# schematic.net
KiCad netlist of a schematic drawn in Altium Designer
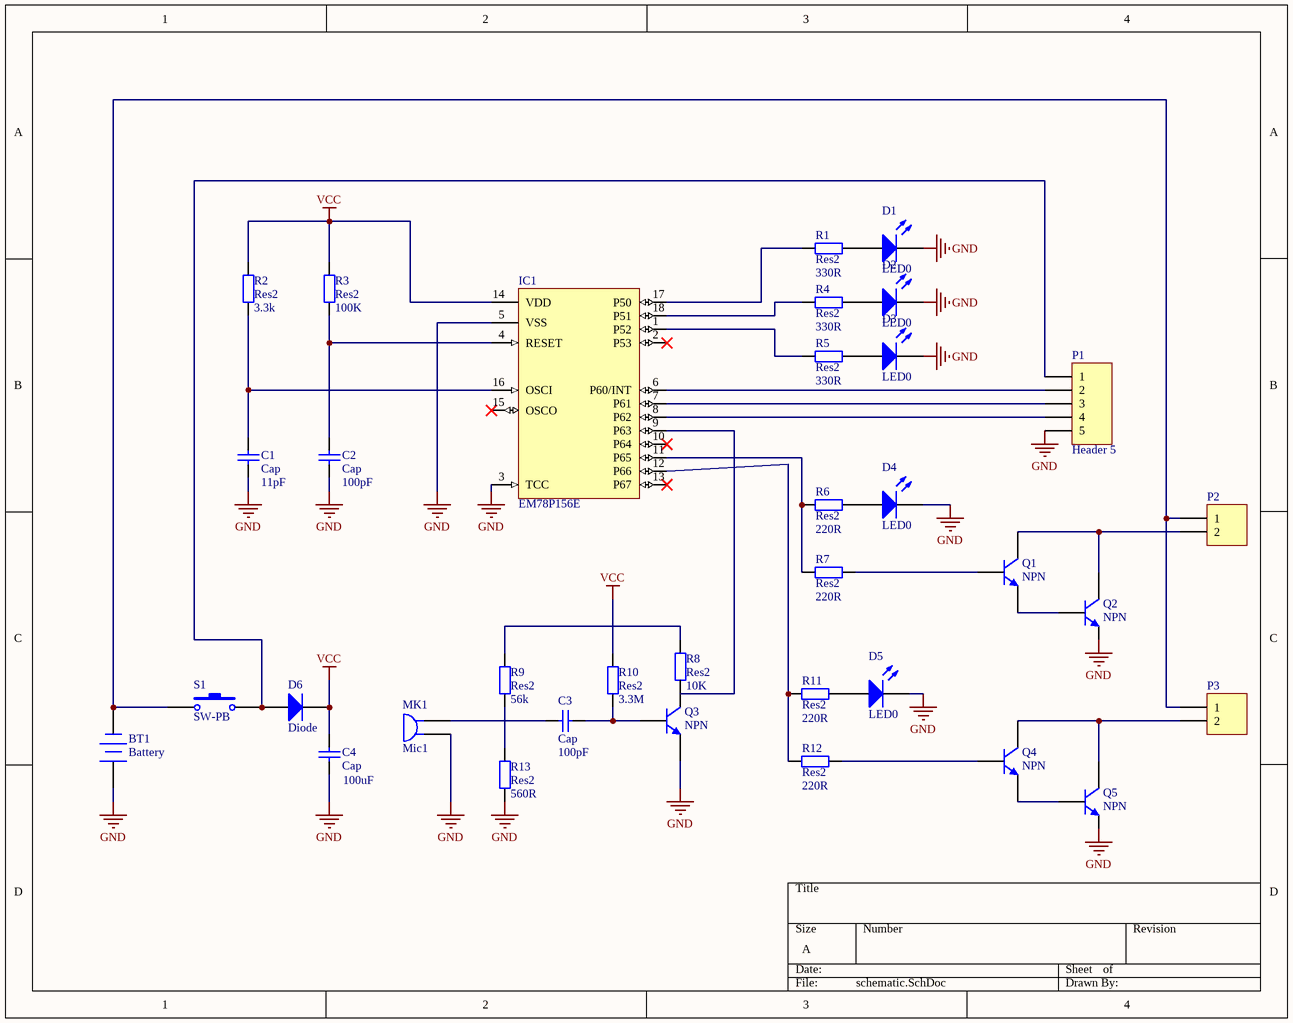
[diagram p0: schematic.SchDoc]

(export (version "E")
  (design (tool "Eeschema 10.0.6"))
  (components
    (comp (ref "BT1")
      (value "Battery")
      (footprint "BAT-2")
      (description "Multicell Battery")
      (fields (field (name "PUBLISHER") "Altium Limited"))
      (libsource (lib "Miscellaneous Devices") (part "Battery"))
    )
    (comp (ref "C1")
      (value "Cap")
      (footprint "RAD-0.3")
      (description "Capacitor")
      (fields (field (name "ALTIUM_VALUE") "11pF") (field (name "PUBLISHER") "Altium Limited"))
      (libsource (lib "Miscellaneous Devices") (part "Cap"))
    )
    (comp (ref "C2")
      (value "Cap")
      (footprint "RAD-0.3")
      (description "Capacitor")
      (fields (field (name "ALTIUM_VALUE") "100pF") (field (name "PUBLISHER") "Altium Limited"))
      (libsource (lib "Miscellaneous Devices") (part "Cap"))
    )
    (comp (ref "C3")
      (value "Cap")
      (footprint "RAD-0.3")
      (description "Capacitor")
      (fields (field (name "ALTIUM_VALUE") "100pF") (field (name "PUBLISHER") "Altium Limited"))
      (libsource (lib "Miscellaneous Devices") (part "Cap"))
    )
    (comp (ref "C4")
      (value "Cap")
      (footprint "RAD-0.3")
      (description "Capacitor")
      (fields (field (name "ALTIUM_VALUE") "100uF") (field (name "PUBLISHER") "Altium Limited"))
      (libsource (lib "Miscellaneous Devices") (part "Cap"))
    )
    (comp (ref "D1")
      (value "LED0")
      (footprint "LED-0")
      (description "Typical INFRARED GaAs LED")
      (fields (field (name "PUBLISHER") "Altium Limited"))
      (libsource (lib "Miscellaneous Devices") (part "LED0"))
    )
    (comp (ref "D2")
      (value "LED0")
      (footprint "LED-0")
      (description "Typical INFRARED GaAs LED")
      (fields (field (name "PUBLISHER") "Altium Limited"))
      (libsource (lib "Miscellaneous Devices") (part "LED0"))
    )
    (comp (ref "D3")
      (value "LED0")
      (footprint "LED-0")
      (description "Typical INFRARED GaAs LED")
      (fields (field (name "PUBLISHER") "Altium Limited"))
      (libsource (lib "Miscellaneous Devices") (part "LED0"))
    )
    (comp (ref "D4")
      (value "LED0")
      (footprint "LED-0")
      (description "Typical INFRARED GaAs LED")
      (fields (field (name "PUBLISHER") "Altium Limited"))
      (libsource (lib "Miscellaneous Devices") (part "LED0"))
    )
    (comp (ref "D5")
      (value "LED0")
      (footprint "LED-0")
      (description "Typical INFRARED GaAs LED")
      (fields (field (name "PUBLISHER") "Altium Limited"))
      (libsource (lib "Miscellaneous Devices") (part "LED0"))
    )
    (comp (ref "D6")
      (value "Diode")
      (footprint "SMC")
      (description "Default Diode")
      (fields (field (name "PUBLISHER") "Altium Limited"))
      (libsource (lib "Miscellaneous Devices") (part "Diode"))
    )
    (comp (ref "IC1")
      (value "EM78P156E")
      (footprint "DIP18")
      (libsource (lib "MC_personal") (part "EM78P156E"))
    )
    (comp (ref "MK1")
      (value "Mic1")
      (footprint "PIN2")
      (description "Microphone")
      (fields (field (name "PUBLISHER") "Altium Limited"))
      (libsource (lib "Miscellaneous Devices") (part "Mic1"))
    )
    (comp (ref "P1")
      (value "Header 5")
      (footprint "HDR1X5")
      (description "Header, 5-Pin")
      (fields (field (name "PUBLISHER") "Altium Limited"))
      (libsource (lib "Miscellaneous Connectors") (part "Header 5"))
    )
    (comp (ref "P2")
      (value "Header 2")
      (footprint "HDR1X2")
      (description "Header, 2-Pin")
      (fields (field (name "PUBLISHER") "Altium Limited"))
      (libsource (lib "MC_personal") (part "Header 2"))
    )
    (comp (ref "P3")
      (value "Header 2")
      (footprint "HDR1X2")
      (description "Header, 2-Pin")
      (fields (field (name "PUBLISHER") "Altium Limited"))
      (libsource (lib "MC_personal") (part "Header 2"))
    )
    (comp (ref "Q1")
      (value "NPN")
      (footprint "TO-226-AA")
      (description "NPN Bipolar Transistor")
      (fields (field (name "PUBLISHER") "Altium Limited"))
      (libsource (lib "Miscellaneous Devices") (part "NPN"))
    )
    (comp (ref "Q2")
      (value "NPN")
      (footprint "TO-226-AA")
      (description "NPN Bipolar Transistor")
      (fields (field (name "PUBLISHER") "Altium Limited"))
      (libsource (lib "Miscellaneous Devices") (part "NPN"))
    )
    (comp (ref "Q3")
      (value "NPN")
      (footprint "TO-226-AA")
      (description "NPN Bipolar Transistor")
      (fields (field (name "PUBLISHER") "Altium Limited"))
      (libsource (lib "Miscellaneous Devices") (part "NPN"))
    )
    (comp (ref "Q4")
      (value "NPN")
      (footprint "TO-226-AA")
      (description "NPN Bipolar Transistor")
      (fields (field (name "PUBLISHER") "Altium Limited"))
      (libsource (lib "Miscellaneous Devices") (part "NPN"))
    )
    (comp (ref "Q5")
      (value "NPN")
      (footprint "TO-226-AA")
      (description "NPN Bipolar Transistor")
      (fields (field (name "PUBLISHER") "Altium Limited"))
      (libsource (lib "Miscellaneous Devices") (part "NPN"))
    )
    (comp (ref "R1")
      (value "Res2")
      (footprint "AXIAL-0.4")
      (description "Resistor")
      (fields (field (name "ALTIUM_VALUE") "330R") (field (name "PUBLISHER") "Altium Limited"))
      (libsource (lib "") (part "Res2_1"))
    )
    (comp (ref "R2")
      (value "Res2")
      (footprint "AXIAL-0.4")
      (description "Resistor")
      (fields (field (name "ALTIUM_VALUE") "3.3k") (field (name "PUBLISHER") "Altium Limited"))
      (libsource (lib "Miscellaneous Devices") (part "Res2"))
    )
    (comp (ref "R3")
      (value "Res2")
      (footprint "AXIAL-0.4")
      (description "Resistor")
      (fields (field (name "ALTIUM_VALUE") "100K") (field (name "PUBLISHER") "Altium Limited"))
      (libsource (lib "Miscellaneous Devices") (part "Res2"))
    )
    (comp (ref "R4")
      (value "Res2")
      (footprint "AXIAL-0.4")
      (description "Resistor")
      (fields (field (name "ALTIUM_VALUE") "330R") (field (name "PUBLISHER") "Altium Limited"))
      (libsource (lib "") (part "Res2_1"))
    )
    (comp (ref "R5")
      (value "Res2")
      (footprint "AXIAL-0.4")
      (description "Resistor")
      (fields (field (name "ALTIUM_VALUE") "330R") (field (name "PUBLISHER") "Altium Limited"))
      (libsource (lib "") (part "Res2_1"))
    )
    (comp (ref "R6")
      (value "Res2")
      (footprint "AXIAL-0.4")
      (description "Resistor")
      (fields (field (name "ALTIUM_VALUE") "220R") (field (name "PUBLISHER") "Altium Limited"))
      (libsource (lib "") (part "Res2_1"))
    )
    (comp (ref "R7")
      (value "Res2")
      (footprint "AXIAL-0.4")
      (description "Resistor")
      (fields (field (name "ALTIUM_VALUE") "220R") (field (name "PUBLISHER") "Altium Limited"))
      (libsource (lib "") (part "Res2_1"))
    )
    (comp (ref "R8")
      (value "Res2")
      (footprint "AXIAL-0.4")
      (description "Resistor")
      (fields (field (name "ALTIUM_VALUE") "10K") (field (name "PUBLISHER") "Altium Limited"))
      (libsource (lib "Miscellaneous Devices") (part "Res2"))
    )
    (comp (ref "R9")
      (value "Res2")
      (footprint "AXIAL-0.4")
      (description "Resistor")
      (fields (field (name "ALTIUM_VALUE") "56k") (field (name "PUBLISHER") "Altium Limited"))
      (libsource (lib "Miscellaneous Devices") (part "Res2"))
    )
    (comp (ref "R10")
      (value "Res2")
      (footprint "AXIAL-0.4")
      (description "Resistor")
      (fields (field (name "ALTIUM_VALUE") "3.3M") (field (name "PUBLISHER") "Altium Limited"))
      (libsource (lib "Miscellaneous Devices") (part "Res2"))
    )
    (comp (ref "R11")
      (value "Res2")
      (footprint "AXIAL-0.4")
      (description "Resistor")
      (fields (field (name "ALTIUM_VALUE") "220R") (field (name "PUBLISHER") "Altium Limited"))
      (libsource (lib "") (part "Res2_1"))
    )
    (comp (ref "R12")
      (value "Res2")
      (footprint "AXIAL-0.4")
      (description "Resistor")
      (fields (field (name "ALTIUM_VALUE") "220R") (field (name "PUBLISHER") "Altium Limited"))
      (libsource (lib "") (part "Res2_1"))
    )
    (comp (ref "R13")
      (value "Res2")
      (footprint "AXIAL-0.4")
      (description "Resistor")
      (fields (field (name "ALTIUM_VALUE") "560R") (field (name "PUBLISHER") "Altium Limited"))
      (libsource (lib "Miscellaneous Devices") (part "Res2"))
    )
    (comp (ref "S1")
      (value "SW-PB")
      (footprint "SPST-2")
      (description "Switch")
      (fields (field (name "PUBLISHER") "Altium Limited"))
      (libsource (lib "Miscellaneous Devices") (part "SW-PB"))
    )
  )
  (nets
    (net (code "1") (name "GND") (class "Default")
      (node (ref "BT1") (pin "1") (pinfunction "+_1") (pintype "passive"))
      (node (ref "C1") (pin "1") (pinfunction "1_1") (pintype "passive"))
      (node (ref "C2") (pin "1") (pinfunction "1_1") (pintype "passive"))
      (node (ref "C4") (pin "1") (pinfunction "1_1") (pintype "passive"))
      (node (ref "D1") (pin "2") (pinfunction "K_2") (pintype "passive"))
      (node (ref "D2") (pin "2") (pinfunction "K_2") (pintype "passive"))
      (node (ref "D3") (pin "2") (pinfunction "K_2") (pintype "passive"))
      (node (ref "D4") (pin "2") (pinfunction "K_2") (pintype "passive"))
      (node (ref "D5") (pin "2") (pinfunction "K_2") (pintype "passive"))
      (node (ref "IC1") (pin "3") (pinfunction "TCC_3") (pintype "input"))
      (node (ref "IC1") (pin "5") (pinfunction "VSS_5") (pintype "passive"))
      (node (ref "MK1") (pin "1") (pinfunction "1_1") (pintype "passive"))
      (node (ref "P1") (pin "5") (pinfunction "5_5") (pintype "passive"))
      (node (ref "Q3") (pin "3") (pinfunction "E_3") (pintype "passive"))
      (node (ref "R13") (pin "1") (pinfunction "1_1") (pintype "passive"))
    )
    (net (code "2") (name "Net-(BT1--)") (class "Default")
      (node (ref "BT1") (pin "2") (pinfunction "-_2") (pintype "passive"))
      (node (ref "P2") (pin "1") (pinfunction "1_1") (pintype "passive"))
      (node (ref "P3") (pin "1") (pinfunction "1_1") (pintype "passive"))
      (node (ref "S1") (pin "1") (pinfunction "1_1") (pintype "passive"))
    )
    (net (code "3") (name "Net-(C3-Pad2)") (class "Default")
      (node (ref "C3") (pin "2") (pinfunction "2_2") (pintype "passive"))
      (node (ref "MK1") (pin "2") (pinfunction "2_2") (pintype "passive"))
    )
    (net (code "4") (name "Net-(D1-A)") (class "Default")
      (node (ref "D1") (pin "1") (pinfunction "A_1") (pintype "passive"))
      (node (ref "R1") (pin "1") (pinfunction "1_1") (pintype "passive"))
    )
    (net (code "5") (name "Net-(D2-A)") (class "Default")
      (node (ref "D2") (pin "1") (pinfunction "A_1") (pintype "passive"))
      (node (ref "R4") (pin "1") (pinfunction "1_1") (pintype "passive"))
    )
    (net (code "6") (name "Net-(D3-A)") (class "Default")
      (node (ref "D3") (pin "1") (pinfunction "A_1") (pintype "passive"))
      (node (ref "R5") (pin "1") (pinfunction "1_1") (pintype "passive"))
    )
    (net (code "7") (name "Net-(D4-A)") (class "Default")
      (node (ref "D4") (pin "1") (pinfunction "A_1") (pintype "passive"))
      (node (ref "R6") (pin "1") (pinfunction "1_1") (pintype "passive"))
    )
    (net (code "8") (name "Net-(D5-A)") (class "Default")
      (node (ref "D5") (pin "1") (pinfunction "A_1") (pintype "passive"))
      (node (ref "R11") (pin "1") (pinfunction "1_1") (pintype "passive"))
    )
    (net (code "9") (name "Net-(D6-A)") (class "Default")
      (node (ref "D6") (pin "1") (pinfunction "A_1") (pintype "passive"))
      (node (ref "P1") (pin "1") (pinfunction "1_1") (pintype "passive"))
      (node (ref "S1") (pin "2") (pinfunction "2_2") (pintype "passive"))
    )
    (net (code "10") (name "Net-(IC1-OSCI)") (class "Default")
      (node (ref "C1") (pin "2") (pinfunction "2_2") (pintype "passive"))
      (node (ref "IC1") (pin "16") (pinfunction "OSCI_16") (pintype "input"))
      (node (ref "R2") (pin "1") (pinfunction "1_1") (pintype "passive"))
    )
    (net (code "11") (name "Net-(IC1-P50)") (class "Default")
      (node (ref "IC1") (pin "17") (pinfunction "P50_17") (pintype "bidirectional"))
      (node (ref "R1") (pin "2") (pinfunction "2_2") (pintype "passive"))
    )
    (net (code "12") (name "Net-(IC1-P51)") (class "Default")
      (node (ref "IC1") (pin "18") (pinfunction "P51_18") (pintype "bidirectional"))
      (node (ref "R4") (pin "2") (pinfunction "2_2") (pintype "passive"))
    )
    (net (code "13") (name "Net-(IC1-P52)") (class "Default")
      (node (ref "IC1") (pin "1") (pinfunction "P52_1") (pintype "bidirectional"))
      (node (ref "R5") (pin "2") (pinfunction "2_2") (pintype "passive"))
    )
    (net (code "14") (name "Net-(IC1-P60{slash}INT)") (class "Default")
      (node (ref "IC1") (pin "6") (pinfunction "P60/INT_6") (pintype "bidirectional"))
      (node (ref "P1") (pin "2") (pinfunction "2_2") (pintype "passive"))
    )
    (net (code "15") (name "Net-(IC1-P61)") (class "Default")
      (node (ref "IC1") (pin "7") (pinfunction "P61_7") (pintype "bidirectional"))
      (node (ref "P1") (pin "3") (pinfunction "3_3") (pintype "passive"))
    )
    (net (code "16") (name "Net-(IC1-P62)") (class "Default")
      (node (ref "IC1") (pin "8") (pinfunction "P62_8") (pintype "bidirectional"))
      (node (ref "P1") (pin "4") (pinfunction "4_4") (pintype "passive"))
    )
    (net (code "17") (name "Net-(IC1-P63)") (class "Default")
      (node (ref "IC1") (pin "9") (pinfunction "P63_9") (pintype "bidirectional"))
      (node (ref "R8") (pin "1") (pinfunction "1_1") (pintype "passive"))
    )
    (net (code "18") (name "Net-(IC1-P65)") (class "Default")
      (node (ref "IC1") (pin "11") (pinfunction "P65_11") (pintype "bidirectional"))
      (node (ref "R6") (pin "2") (pinfunction "2_2") (pintype "passive"))
      (node (ref "R7") (pin "2") (pinfunction "2_2") (pintype "passive"))
    )
    (net (code "19") (name "Net-(IC1-P66)") (class "Default")
      (node (ref "IC1") (pin "12") (pinfunction "P66_12") (pintype "bidirectional"))
      (node (ref "R11") (pin "2") (pinfunction "2_2") (pintype "passive"))
      (node (ref "R12") (pin "2") (pinfunction "2_2") (pintype "passive"))
    )
    (net (code "20") (name "Net-(IC1-RESET)") (class "Default")
      (node (ref "C2") (pin "2") (pinfunction "2_2") (pintype "passive"))
      (node (ref "IC1") (pin "4") (pinfunction "RESET_4") (pintype "input"))
      (node (ref "R3") (pin "1") (pinfunction "1_1") (pintype "passive"))
    )
    (net (code "21") (name "Net-(Q1-B)") (class "Default")
      (node (ref "Q1") (pin "2") (pinfunction "B_2") (pintype "passive"))
      (node (ref "R7") (pin "1") (pinfunction "1_1") (pintype "passive"))
    )
    (net (code "22") (name "Net-(Q1-C)") (class "Default")
      (node (ref "P2") (pin "2") (pinfunction "2_2") (pintype "passive"))
      (node (ref "Q1") (pin "1") (pinfunction "C_1") (pintype "passive"))
      (node (ref "Q2") (pin "1") (pinfunction "C_1") (pintype "passive"))
    )
    (net (code "23") (name "Net-(Q1-E)") (class "Default")
      (node (ref "Q1") (pin "3") (pinfunction "E_3") (pintype "passive"))
      (node (ref "Q2") (pin "2") (pinfunction "B_2") (pintype "passive"))
    )
    (net (code "24") (name "Net-(Q3-B)") (class "Default")
      (node (ref "C3") (pin "1") (pinfunction "1_1") (pintype "passive"))
      (node (ref "Q3") (pin "2") (pinfunction "B_2") (pintype "passive"))
      (node (ref "R10") (pin "1") (pinfunction "1_1") (pintype "passive"))
    )
    (net (code "25") (name "Net-(Q4-B)") (class "Default")
      (node (ref "Q4") (pin "2") (pinfunction "B_2") (pintype "passive"))
      (node (ref "R12") (pin "1") (pinfunction "1_1") (pintype "passive"))
    )
    (net (code "26") (name "Net-(Q4-C)") (class "Default")
      (node (ref "P3") (pin "2") (pinfunction "2_2") (pintype "passive"))
      (node (ref "Q4") (pin "1") (pinfunction "C_1") (pintype "passive"))
      (node (ref "Q5") (pin "1") (pinfunction "C_1") (pintype "passive"))
    )
    (net (code "27") (name "Net-(Q4-E)") (class "Default")
      (node (ref "Q4") (pin "3") (pinfunction "E_3") (pintype "passive"))
      (node (ref "Q5") (pin "2") (pinfunction "B_2") (pintype "passive"))
    )
    (net (code "28") (name "Net-(R8-Pad2)") (class "Default")
      (node (ref "R8") (pin "2") (pinfunction "2_2") (pintype "passive"))
      (node (ref "R9") (pin "2") (pinfunction "2_2") (pintype "passive"))
    )
    (net (code "29") (name "Net-(R13-Pad2)") (class "Default")
      (node (ref "R13") (pin "2") (pinfunction "2_2") (pintype "passive"))
      (node (ref "R9") (pin "1") (pinfunction "1_1") (pintype "passive"))
    )
    (net (code "30") (name "VCC") (class "Default")
      (node (ref "C4") (pin "2") (pinfunction "2_2") (pintype "passive"))
      (node (ref "D6") (pin "2") (pinfunction "K_2") (pintype "passive"))
      (node (ref "IC1") (pin "14") (pinfunction "VDD_14") (pintype "passive"))
      (node (ref "R10") (pin "2") (pinfunction "2_2") (pintype "passive"))
      (node (ref "R2") (pin "2") (pinfunction "2_2") (pintype "passive"))
      (node (ref "R3") (pin "2") (pinfunction "2_2") (pintype "passive"))
    )
    (net (code "31") (name "unconnected-(IC1-OSCO-Pad15)") (class "Default")
      (node (ref "IC1") (pin "15") (pinfunction "OSCO_15") (pintype "bidirectional+no_connect"))
    )
    (net (code "32") (name "unconnected-(IC1-P53-Pad2)") (class "Default")
      (node (ref "IC1") (pin "2") (pinfunction "P53_2") (pintype "bidirectional+no_connect"))
    )
    (net (code "33") (name "unconnected-(IC1-P64-Pad10)") (class "Default")
      (node (ref "IC1") (pin "10") (pinfunction "P64_10") (pintype "bidirectional+no_connect"))
    )
    (net (code "34") (name "unconnected-(IC1-P67-Pad13)") (class "Default")
      (node (ref "IC1") (pin "13") (pinfunction "P67_13") (pintype "bidirectional+no_connect"))
    )
    (net (code "35") (name "unconnected-(Q2-E-Pad3)") (class "Default")
      (node (ref "Q2") (pin "3") (pinfunction "E_3") (pintype "passive"))
    )
    (net (code "36") (name "unconnected-(Q3-C-Pad1)") (class "Default")
      (node (ref "Q3") (pin "1") (pinfunction "C_1") (pintype "passive"))
    )
    (net (code "37") (name "unconnected-(Q5-E-Pad3)") (class "Default")
      (node (ref "Q5") (pin "3") (pinfunction "E_3") (pintype "passive"))
    )
  )
)
